# PSU.net
KiCad netlist of a schematic drawn in EAGLE
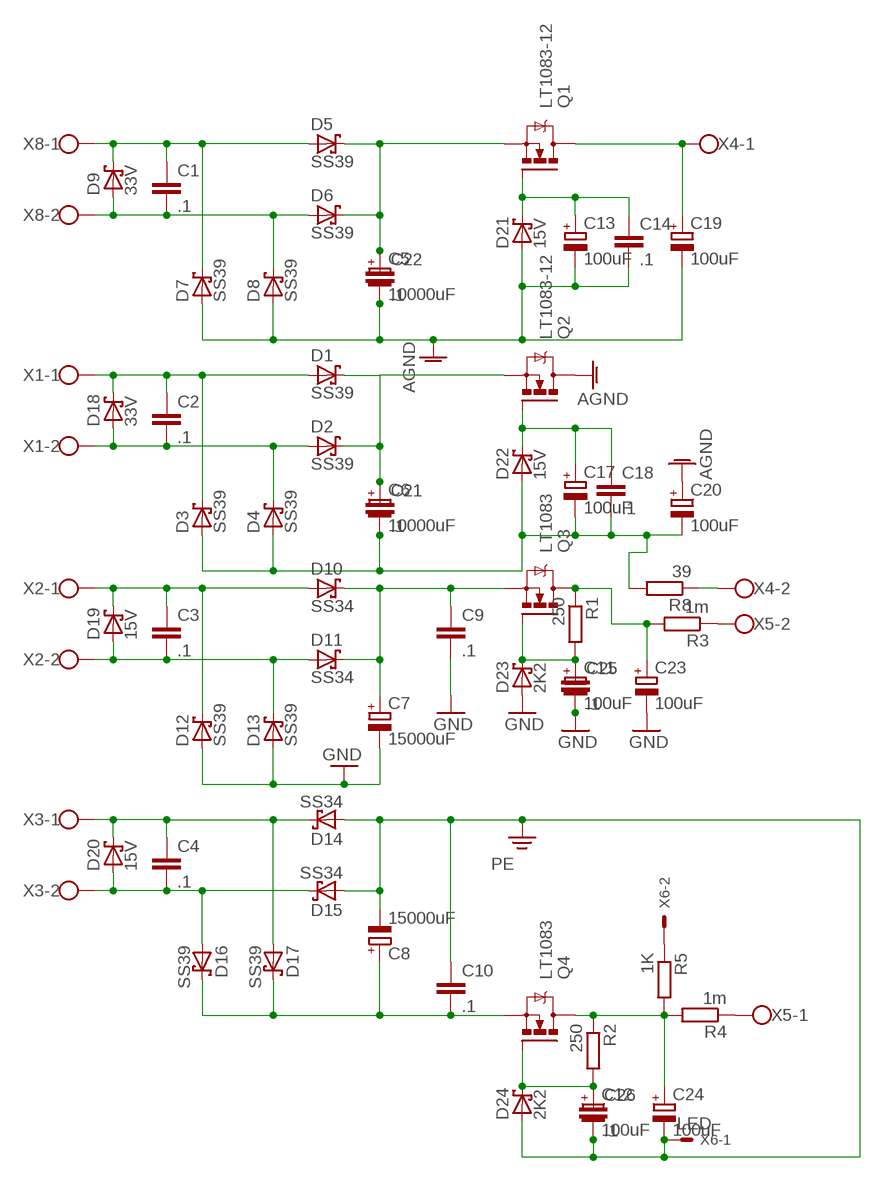
[diagram p0: schematic, sheet 1]

(export (version "E")
  (design (tool "Eeschema 10.0.6"))
  (components
    (comp (ref "C1")
      (value ".1")
      (footprint "eagle-import:C075-042X103")
      (libsource (lib "eagle-import") (part "C-EU075-042X103"))
    )
    (comp (ref "C2")
      (value ".1")
      (footprint "eagle-import:C075-042X103")
      (libsource (lib "eagle-import") (part "C-EU075-042X103"))
    )
    (comp (ref "C3")
      (value ".1")
      (footprint "eagle-import:C075-042X103")
      (libsource (lib "eagle-import") (part "C-EU075-042X103"))
    )
    (comp (ref "C4")
      (value ".1")
      (footprint "eagle-import:C075-042X103")
      (libsource (lib "eagle-import") (part "C-EU075-042X103"))
    )
    (comp (ref "C5")
      (value "10000uF")
      (footprint "eagle-import:EB25D")
      (libsource (lib "eagle-import") (part "CPOL-EUE10-25"))
    )
    (comp (ref "C6")
      (value "10000uF")
      (footprint "eagle-import:EB25D")
      (libsource (lib "eagle-import") (part "CPOL-EUE10-25"))
    )
    (comp (ref "C7")
      (value "15000uF")
      (footprint "eagle-import:EB25D")
      (libsource (lib "eagle-import") (part "CPOL-EUE10-25"))
    )
    (comp (ref "C8")
      (value "15000uF")
      (footprint "eagle-import:EB25D")
      (libsource (lib "eagle-import") (part "CPOL-EUE10-25"))
    )
    (comp (ref "C9")
      (value ".1")
      (footprint "eagle-import:C1210K")
      (libsource (lib "eagle-import") (part "C-EUC1210K"))
    )
    (comp (ref "C10")
      (value ".1")
      (footprint "eagle-import:C1210K")
      (libsource (lib "eagle-import") (part "C-EUC1210K"))
    )
    (comp (ref "C11")
      (value "100uF")
      (footprint "eagle-import:E5-10,5")
      (libsource (lib "eagle-import") (part "CPOL-EUE5-10.5"))
    )
    (comp (ref "C12")
      (value "100uF")
      (footprint "eagle-import:E5-10,5")
      (libsource (lib "eagle-import") (part "CPOL-EUE5-10.5"))
    )
    (comp (ref "C13")
      (value "100uF")
      (footprint "eagle-import:E5-10,5")
      (libsource (lib "eagle-import") (part "CPOL-EUE5-10.5"))
    )
    (comp (ref "C14")
      (value ".1")
      (footprint "eagle-import:C1210K")
      (libsource (lib "eagle-import") (part "C-EUC1210K"))
    )
    (comp (ref "C17")
      (value "100uF")
      (footprint "eagle-import:E5-10,5")
      (libsource (lib "eagle-import") (part "CPOL-EUE5-10.5"))
    )
    (comp (ref "C18")
      (value ".1")
      (footprint "eagle-import:C1210K")
      (libsource (lib "eagle-import") (part "C-EUC1210K"))
    )
    (comp (ref "C19")
      (value "100uF")
      (footprint "eagle-import:E5-10,5")
      (libsource (lib "eagle-import") (part "CPOL-EUE5-10.5"))
    )
    (comp (ref "C20")
      (value "100uF")
      (footprint "eagle-import:E5-10,5")
      (libsource (lib "eagle-import") (part "CPOL-EUE5-10.5"))
    )
    (comp (ref "C21")
      (value ".1")
      (footprint "eagle-import:C1210K")
      (libsource (lib "eagle-import") (part "C-EUC1210K"))
    )
    (comp (ref "C22")
      (value ".1")
      (footprint "eagle-import:C1210K")
      (libsource (lib "eagle-import") (part "C-EUC1210K"))
    )
    (comp (ref "C23")
      (value "100uF")
      (footprint "eagle-import:E5-10,5")
      (libsource (lib "eagle-import") (part "CPOL-EUE5-10.5"))
    )
    (comp (ref "C24")
      (value "100uF")
      (footprint "eagle-import:E5-10,5")
      (libsource (lib "eagle-import") (part "CPOL-EUE5-10.5"))
    )
    (comp (ref "C25")
      (value ".1")
      (footprint "eagle-import:C1210K")
      (libsource (lib "eagle-import") (part "C-EUC1210K"))
    )
    (comp (ref "C26")
      (value ".1")
      (footprint "eagle-import:C1210K")
      (libsource (lib "eagle-import") (part "C-EUC1210K"))
    )
    (comp (ref "D1")
      (value "SS39")
      (footprint "eagle-import:SMC")
      (libsource (lib "eagle-import") (part "MBRS30T32"))
    )
    (comp (ref "D2")
      (value "SS39")
      (footprint "eagle-import:SMC")
      (libsource (lib "eagle-import") (part "MBRS30T32"))
    )
    (comp (ref "D3")
      (value "SS39")
      (footprint "eagle-import:SMC")
      (libsource (lib "eagle-import") (part "MBRS30T32"))
    )
    (comp (ref "D4")
      (value "SS39")
      (footprint "eagle-import:SMC")
      (libsource (lib "eagle-import") (part "MBRS30T32"))
    )
    (comp (ref "D5")
      (value "SS39")
      (footprint "eagle-import:SMC")
      (libsource (lib "eagle-import") (part "MBRS30T32"))
    )
    (comp (ref "D6")
      (value "SS39")
      (footprint "eagle-import:SMC")
      (libsource (lib "eagle-import") (part "MBRS30T32"))
    )
    (comp (ref "D7")
      (value "SS39")
      (footprint "eagle-import:SMC")
      (libsource (lib "eagle-import") (part "MBRS30T32"))
    )
    (comp (ref "D8")
      (value "SS39")
      (footprint "eagle-import:SMC")
      (libsource (lib "eagle-import") (part "MBRS30T32"))
    )
    (comp (ref "D9")
      (value "33V")
      (footprint "eagle-import:SMB")
      (libsource (lib "eagle-import") (part "MBRS130LT3"))
    )
    (comp (ref "D10")
      (value "SS34")
      (footprint "eagle-import:SMC")
      (libsource (lib "eagle-import") (part "MBRS30T32"))
    )
    (comp (ref "D11")
      (value "SS34")
      (footprint "eagle-import:SMC")
      (libsource (lib "eagle-import") (part "MBRS30T32"))
    )
    (comp (ref "D12")
      (value "SS39")
      (footprint "eagle-import:SMC")
      (libsource (lib "eagle-import") (part "MBRS30T32"))
    )
    (comp (ref "D13")
      (value "SS39")
      (footprint "eagle-import:SMC")
      (libsource (lib "eagle-import") (part "MBRS30T32"))
    )
    (comp (ref "D14")
      (value "SS34")
      (footprint "eagle-import:SMC")
      (libsource (lib "eagle-import") (part "MBRS30T32"))
    )
    (comp (ref "D15")
      (value "SS34")
      (footprint "eagle-import:SMC")
      (libsource (lib "eagle-import") (part "MBRS30T32"))
    )
    (comp (ref "D16")
      (value "SS39")
      (footprint "eagle-import:SMC")
      (libsource (lib "eagle-import") (part "MBRS30T32"))
    )
    (comp (ref "D17")
      (value "SS39")
      (footprint "eagle-import:SMC")
      (libsource (lib "eagle-import") (part "MBRS30T32"))
    )
    (comp (ref "D18")
      (value "33V")
      (footprint "eagle-import:SMB")
      (libsource (lib "eagle-import") (part "MBRS130LT3"))
    )
    (comp (ref "D19")
      (value "15V")
      (footprint "eagle-import:SMB")
      (libsource (lib "eagle-import") (part "MBRS130LT3"))
    )
    (comp (ref "D20")
      (value "15V")
      (footprint "eagle-import:SMB")
      (libsource (lib "eagle-import") (part "MBRS130LT3"))
    )
    (comp (ref "D21")
      (value "15V")
      (footprint "eagle-import:SMB")
      (libsource (lib "eagle-import") (part "MBRS130LT3"))
    )
    (comp (ref "D22")
      (value "15V")
      (footprint "eagle-import:SMB")
      (libsource (lib "eagle-import") (part "MBRS130LT3"))
    )
    (comp (ref "D23")
      (value "2K2")
      (footprint "eagle-import:SMB")
      (libsource (lib "eagle-import") (part "MBRS130LT3"))
    )
    (comp (ref "D24")
      (value "2K2")
      (footprint "eagle-import:SMB")
      (libsource (lib "eagle-import") (part "MBRS130LT3"))
    )
    (comp (ref "Q1")
      (value "LT1083-12")
      (footprint "eagle-import:TO-247AD-H")
      (libsource (lib "eagle-import") (part "IXF?6NH_90"))
    )
    (comp (ref "Q2")
      (value "LT1083-12")
      (footprint "eagle-import:TO-247AD-H")
      (libsource (lib "eagle-import") (part "IXF?6NH_90"))
    )
    (comp (ref "Q3")
      (value "LT1083")
      (footprint "eagle-import:TO-247AD-H")
      (libsource (lib "eagle-import") (part "IXF?6NH_90"))
    )
    (comp (ref "Q4")
      (value "LT1083")
      (footprint "eagle-import:TO-247AD-H")
      (libsource (lib "eagle-import") (part "IXF?6NH_90"))
    )
    (comp (ref "R1")
      (value "250")
      (footprint "eagle-import:R1210")
      (libsource (lib "eagle-import") (part "R-EU_R1210"))
    )
    (comp (ref "R2")
      (value "250")
      (footprint "eagle-import:R1210")
      (libsource (lib "eagle-import") (part "R-EU_R1210"))
    )
    (comp (ref "R3")
      (value "1m")
      (footprint "eagle-import:0309_12")
      (libsource (lib "eagle-import") (part "R-EU_0309/12"))
    )
    (comp (ref "R4")
      (value "1m")
      (footprint "eagle-import:0309_12")
      (libsource (lib "eagle-import") (part "R-EU_0309/12"))
    )
    (comp (ref "R5")
      (value "1K")
      (footprint "eagle-import:R1210")
      (libsource (lib "eagle-import") (part "R-EU_R1210"))
    )
    (comp (ref "R8")
      (value "39")
      (footprint "eagle-import:0309_12")
      (libsource (lib "eagle-import") (part "R-EU_0309/12"))
    )
    (comp (ref "X1")
      (value "W237-102")
      (footprint "eagle-import:W237-102")
      (fields
        (field (name "MPN") "237-102")
        (field (name "MPN_1") "237-102")
        (field (name "OC_FARNELL") "unknown")
        (field (name "OC_NEWARK") "70K9898")
      )
      (libsource (lib "eagle-import") (part "W237-102"))
    )
    (comp (ref "X2")
      (value "W237-102")
      (footprint "eagle-import:W237-102")
      (fields
        (field (name "MPN") "237-102")
        (field (name "MPN_1") "237-102")
        (field (name "OC_FARNELL") "unknown")
        (field (name "OC_NEWARK") "70K9898")
      )
      (libsource (lib "eagle-import") (part "W237-102"))
    )
    (comp (ref "X3")
      (value "W237-102")
      (footprint "eagle-import:W237-102")
      (fields
        (field (name "MPN") "237-102")
        (field (name "MPN_1") "237-102")
        (field (name "OC_FARNELL") "unknown")
        (field (name "OC_NEWARK") "70K9898")
      )
      (libsource (lib "eagle-import") (part "W237-102"))
    )
    (comp (ref "X4")
      (value "W237-102")
      (footprint "eagle-import:W237-102")
      (fields
        (field (name "MPN") "237-102")
        (field (name "MPN_1") "237-102")
        (field (name "OC_FARNELL") "unknown")
        (field (name "OC_NEWARK") "70K9898")
      )
      (libsource (lib "eagle-import") (part "W237-102"))
    )
    (comp (ref "X5")
      (value "W237-102")
      (footprint "eagle-import:W237-102")
      (fields
        (field (name "MPN") "237-102")
        (field (name "MPN_1") "237-102")
        (field (name "OC_FARNELL") "unknown")
        (field (name "OC_NEWARK") "70K9898")
      )
      (libsource (lib "eagle-import") (part "W237-102"))
    )
    (comp (ref "X6")
      (value "LED")
      (footprint "eagle-import:22-23-2021")
      (fields (field (name "MF") "MOLEX") (field (name "MPN") "22-23-2021"))
      (libsource (lib "eagle-import") (part "22-23-2021"))
    )
    (comp (ref "X8")
      (value "W237-102")
      (footprint "eagle-import:W237-102")
      (fields
        (field (name "MPN") "237-102")
        (field (name "MPN_1") "237-102")
        (field (name "OC_FARNELL") "unknown")
        (field (name "OC_NEWARK") "70K9898")
      )
      (libsource (lib "eagle-import") (part "W237-102"))
    )
  )
  (nets
    (net (code "1") (name "AGND") (class "Default")
      (node (ref "C13") (pin "-") (pinfunction "-_-") (pintype "passive"))
      (node (ref "C14") (pin "2") (pinfunction "2_2") (pintype "passive"))
      (node (ref "C19") (pin "-") (pinfunction "-_-") (pintype "passive"))
      (node (ref "C20") (pin "+") (pinfunction "+_+") (pintype "passive"))
      (node (ref "C22") (pin "2") (pinfunction "2_2") (pintype "passive"))
      (node (ref "C5") (pin "-") (pinfunction "-_-") (pintype "passive"))
      (node (ref "D21") (pin "A") (pinfunction "A_A") (pintype "passive"))
      (node (ref "D7") (pin "A") (pinfunction "A_A") (pintype "passive"))
      (node (ref "D8") (pin "A") (pinfunction "A_A") (pintype "passive"))
      (node (ref "Q2") (pin "D") (pinfunction "D_D") (pintype "passive"))
    )
    (net (code "2") (name "GND") (class "Default")
      (node (ref "C11") (pin "-") (pinfunction "-_-") (pintype "passive"))
      (node (ref "C23") (pin "-") (pinfunction "-_-") (pintype "passive"))
      (node (ref "C25") (pin "2") (pinfunction "2_2") (pintype "passive"))
      (node (ref "C7") (pin "-") (pinfunction "-_-") (pintype "passive"))
      (node (ref "C9") (pin "2") (pinfunction "2_2") (pintype "passive"))
      (node (ref "D12") (pin "A") (pinfunction "A_A") (pintype "passive"))
      (node (ref "D13") (pin "A") (pinfunction "A_A") (pintype "passive"))
      (node (ref "D23") (pin "A") (pinfunction "A_A") (pintype "passive"))
    )
    (net (code "3") (name "Net-(C7-Pad+)") (class "Default")
      (node (ref "C7") (pin "+") (pinfunction "+_+") (pintype "passive"))
      (node (ref "C9") (pin "1") (pinfunction "1_1") (pintype "passive"))
      (node (ref "D10") (pin "C") (pinfunction "C_C") (pintype "passive"))
      (node (ref "D11") (pin "C") (pinfunction "C_C") (pintype "passive"))
      (node (ref "Q3") (pin "S") (pinfunction "S_S") (pintype "passive"))
    )
    (net (code "4") (name "Net-(C10-Pad2)") (class "Default")
      (node (ref "C10") (pin "2") (pinfunction "2_2") (pintype "passive"))
      (node (ref "C8") (pin "+") (pinfunction "+_+") (pintype "passive"))
      (node (ref "D16") (pin "C") (pinfunction "C_C") (pintype "passive"))
      (node (ref "D17") (pin "C") (pinfunction "C_C") (pintype "passive"))
      (node (ref "Q4") (pin "S") (pinfunction "S_S") (pintype "passive"))
    )
    (net (code "5") (name "Net-(C11-Pad+)") (class "Default")
      (node (ref "C11") (pin "+") (pinfunction "+_+") (pintype "passive"))
      (node (ref "C25") (pin "1") (pinfunction "1_1") (pintype "passive"))
      (node (ref "D23") (pin "C") (pinfunction "C_C") (pintype "passive"))
      (node (ref "Q3") (pin "G") (pinfunction "G_G") (pintype "passive"))
      (node (ref "R1") (pin "2") (pinfunction "2_2") (pintype "passive"))
    )
    (net (code "6") (name "Net-(C12-Pad+)") (class "Default")
      (node (ref "C12") (pin "+") (pinfunction "+_+") (pintype "passive"))
      (node (ref "C26") (pin "1") (pinfunction "1_1") (pintype "passive"))
      (node (ref "D24") (pin "C") (pinfunction "C_C") (pintype "passive"))
      (node (ref "Q4") (pin "G") (pinfunction "G_G") (pintype "passive"))
      (node (ref "R2") (pin "2") (pinfunction "2_2") (pintype "passive"))
    )
    (net (code "7") (name "Net-(C13-Pad+)") (class "Default")
      (node (ref "C13") (pin "+") (pinfunction "+_+") (pintype "passive"))
      (node (ref "C14") (pin "1") (pinfunction "1_1") (pintype "passive"))
      (node (ref "D21") (pin "C") (pinfunction "C_C") (pintype "passive"))
      (node (ref "Q1") (pin "G") (pinfunction "G_G") (pintype "passive"))
    )
    (net (code "8") (name "Net-(C17-Pad+)") (class "Default")
      (node (ref "C17") (pin "+") (pinfunction "+_+") (pintype "passive"))
      (node (ref "C18") (pin "1") (pinfunction "1_1") (pintype "passive"))
      (node (ref "D22") (pin "C") (pinfunction "C_C") (pintype "passive"))
      (node (ref "Q2") (pin "G") (pinfunction "G_G") (pintype "passive"))
    )
    (net (code "9") (name "Net-(C17-Pad-)") (class "Default")
      (node (ref "C17") (pin "-") (pinfunction "-_-") (pintype "passive"))
      (node (ref "C18") (pin "2") (pinfunction "2_2") (pintype "passive"))
      (node (ref "C20") (pin "-") (pinfunction "-_-") (pintype "passive"))
      (node (ref "C21") (pin "2") (pinfunction "2_2") (pintype "passive"))
      (node (ref "C6") (pin "-") (pinfunction "-_-") (pintype "passive"))
      (node (ref "D22") (pin "A") (pinfunction "A_A") (pintype "passive"))
      (node (ref "D3") (pin "A") (pinfunction "A_A") (pintype "passive"))
      (node (ref "D4") (pin "A") (pinfunction "A_A") (pintype "passive"))
      (node (ref "R8") (pin "2") (pinfunction "2_2") (pintype "passive"))
    )
    (net (code "10") (name "Net-(C21-Pad1)") (class "Default")
      (node (ref "C21") (pin "1") (pinfunction "1_1") (pintype "passive"))
      (node (ref "C6") (pin "+") (pinfunction "+_+") (pintype "passive"))
      (node (ref "D1") (pin "C") (pinfunction "C_C") (pintype "passive"))
      (node (ref "D2") (pin "C") (pinfunction "C_C") (pintype "passive"))
      (node (ref "Q2") (pin "S") (pinfunction "S_S") (pintype "passive"))
    )
    (net (code "11") (name "Net-(C22-Pad1)") (class "Default")
      (node (ref "C22") (pin "1") (pinfunction "1_1") (pintype "passive"))
      (node (ref "C5") (pin "+") (pinfunction "+_+") (pintype "passive"))
      (node (ref "D5") (pin "C") (pinfunction "C_C") (pintype "passive"))
      (node (ref "D6") (pin "C") (pinfunction "C_C") (pintype "passive"))
      (node (ref "Q1") (pin "S") (pinfunction "S_S") (pintype "passive"))
    )
    (net (code "12") (name "Net-(C23-Pad+)") (class "Default")
      (node (ref "C23") (pin "+") (pinfunction "+_+") (pintype "passive"))
      (node (ref "Q3") (pin "D") (pinfunction "D_D") (pintype "passive"))
      (node (ref "R1") (pin "1") (pinfunction "1_1") (pintype "passive"))
      (node (ref "R3") (pin "2") (pinfunction "2_2") (pintype "passive"))
    )
    (net (code "13") (name "Net-(C24-Pad+)") (class "Default")
      (node (ref "C24") (pin "+") (pinfunction "+_+") (pintype "passive"))
      (node (ref "Q4") (pin "D") (pinfunction "D_D") (pintype "passive"))
      (node (ref "R2") (pin "1") (pinfunction "1_1") (pintype "passive"))
      (node (ref "R4") (pin "2") (pinfunction "2_2") (pintype "passive"))
      (node (ref "R5") (pin "2") (pinfunction "2_2") (pintype "passive"))
    )
    (net (code "14") (name "Net-(X1A-KL)") (class "Default")
      (node (ref "C2") (pin "1") (pinfunction "1_1") (pintype "passive"))
      (node (ref "D1") (pin "A") (pinfunction "A_A") (pintype "passive"))
      (node (ref "D18") (pin "C") (pinfunction "C_C") (pintype "passive"))
      (node (ref "D3") (pin "C") (pinfunction "C_C") (pintype "passive"))
      (node (ref "X1") (pin "1") (pinfunction "KL_1") (pintype "passive"))
    )
    (net (code "15") (name "Net-(X1B-KL)") (class "Default")
      (node (ref "C2") (pin "2") (pinfunction "2_2") (pintype "passive"))
      (node (ref "D18") (pin "A") (pinfunction "A_A") (pintype "passive"))
      (node (ref "D2") (pin "A") (pinfunction "A_A") (pintype "passive"))
      (node (ref "D4") (pin "C") (pinfunction "C_C") (pintype "passive"))
      (node (ref "X1") (pin "2") (pinfunction "KL_2") (pintype "passive"))
    )
    (net (code "16") (name "Net-(X2A-KL)") (class "Default")
      (node (ref "C3") (pin "1") (pinfunction "1_1") (pintype "passive"))
      (node (ref "D10") (pin "A") (pinfunction "A_A") (pintype "passive"))
      (node (ref "D12") (pin "C") (pinfunction "C_C") (pintype "passive"))
      (node (ref "D19") (pin "C") (pinfunction "C_C") (pintype "passive"))
      (node (ref "X2") (pin "1") (pinfunction "KL_1") (pintype "passive"))
    )
    (net (code "17") (name "Net-(X2B-KL)") (class "Default")
      (node (ref "C3") (pin "2") (pinfunction "2_2") (pintype "passive"))
      (node (ref "D11") (pin "A") (pinfunction "A_A") (pintype "passive"))
      (node (ref "D13") (pin "C") (pinfunction "C_C") (pintype "passive"))
      (node (ref "D19") (pin "A") (pinfunction "A_A") (pintype "passive"))
      (node (ref "X2") (pin "2") (pinfunction "KL_2") (pintype "passive"))
    )
    (net (code "18") (name "Net-(X3A-KL)") (class "Default")
      (node (ref "C4") (pin "1") (pinfunction "1_1") (pintype "passive"))
      (node (ref "D14") (pin "C") (pinfunction "C_C") (pintype "passive"))
      (node (ref "D17") (pin "A") (pinfunction "A_A") (pintype "passive"))
      (node (ref "D20") (pin "C") (pinfunction "C_C") (pintype "passive"))
      (node (ref "X3") (pin "1") (pinfunction "KL_1") (pintype "passive"))
    )
    (net (code "19") (name "Net-(X3B-KL)") (class "Default")
      (node (ref "C4") (pin "2") (pinfunction "2_2") (pintype "passive"))
      (node (ref "D15") (pin "C") (pinfunction "C_C") (pintype "passive"))
      (node (ref "D16") (pin "A") (pinfunction "A_A") (pintype "passive"))
      (node (ref "D20") (pin "A") (pinfunction "A_A") (pintype "passive"))
      (node (ref "X3") (pin "2") (pinfunction "KL_2") (pintype "passive"))
    )
    (net (code "20") (name "Net-(X4A-KL)") (class "Default")
      (node (ref "C19") (pin "+") (pinfunction "+_+") (pintype "passive"))
      (node (ref "Q1") (pin "D") (pinfunction "D_D") (pintype "passive"))
      (node (ref "X4") (pin "1") (pinfunction "KL_1") (pintype "passive"))
    )
    (net (code "21") (name "Net-(X4B-KL)") (class "Default")
      (node (ref "R8") (pin "1") (pinfunction "1_1") (pintype "passive"))
      (node (ref "X4") (pin "2") (pinfunction "KL_2") (pintype "passive"))
    )
    (net (code "22") (name "Net-(X5A-KL)") (class "Default")
      (node (ref "R4") (pin "1") (pinfunction "1_1") (pintype "passive"))
      (node (ref "X5") (pin "1") (pinfunction "KL_1") (pintype "passive"))
    )
    (net (code "23") (name "Net-(X5B-KL)") (class "Default")
      (node (ref "R3") (pin "1") (pinfunction "1_1") (pintype "passive"))
      (node (ref "X5") (pin "2") (pinfunction "KL_2") (pintype "passive"))
    )
    (net (code "24") (name "Net-(X6B-S)") (class "Default")
      (node (ref "R5") (pin "1") (pinfunction "1_1") (pintype "passive"))
      (node (ref "X6") (pin "2") (pinfunction "S_2") (pintype "passive"))
    )
    (net (code "25") (name "Net-(X8A-KL)") (class "Default")
      (node (ref "C1") (pin "1") (pinfunction "1_1") (pintype "passive"))
      (node (ref "D5") (pin "A") (pinfunction "A_A") (pintype "passive"))
      (node (ref "D7") (pin "C") (pinfunction "C_C") (pintype "passive"))
      (node (ref "D9") (pin "C") (pinfunction "C_C") (pintype "passive"))
      (node (ref "X8") (pin "1") (pinfunction "KL_1") (pintype "passive"))
    )
    (net (code "26") (name "Net-(X8B-KL)") (class "Default")
      (node (ref "C1") (pin "2") (pinfunction "2_2") (pintype "passive"))
      (node (ref "D6") (pin "A") (pinfunction "A_A") (pintype "passive"))
      (node (ref "D8") (pin "C") (pinfunction "C_C") (pintype "passive"))
      (node (ref "D9") (pin "A") (pinfunction "A_A") (pintype "passive"))
      (node (ref "X8") (pin "2") (pinfunction "KL_2") (pintype "passive"))
    )
    (net (code "27") (name "PE") (class "Default")
      (node (ref "C10") (pin "1") (pinfunction "1_1") (pintype "passive"))
      (node (ref "C12") (pin "-") (pinfunction "-_-") (pintype "passive"))
      (node (ref "C24") (pin "-") (pinfunction "-_-") (pintype "passive"))
      (node (ref "C26") (pin "2") (pinfunction "2_2") (pintype "passive"))
      (node (ref "C8") (pin "-") (pinfunction "-_-") (pintype "passive"))
      (node (ref "D14") (pin "A") (pinfunction "A_A") (pintype "passive"))
      (node (ref "D15") (pin "A") (pinfunction "A_A") (pintype "passive"))
      (node (ref "D24") (pin "A") (pinfunction "A_A") (pintype "passive"))
      (node (ref "X6") (pin "1") (pinfunction "S_1") (pintype "passive"))
    )
  )
)
